# UBX_NORA_B1_SCHEM_0006_Accessories.net
KiCad netlist of a schematic drawn in Altium Designer
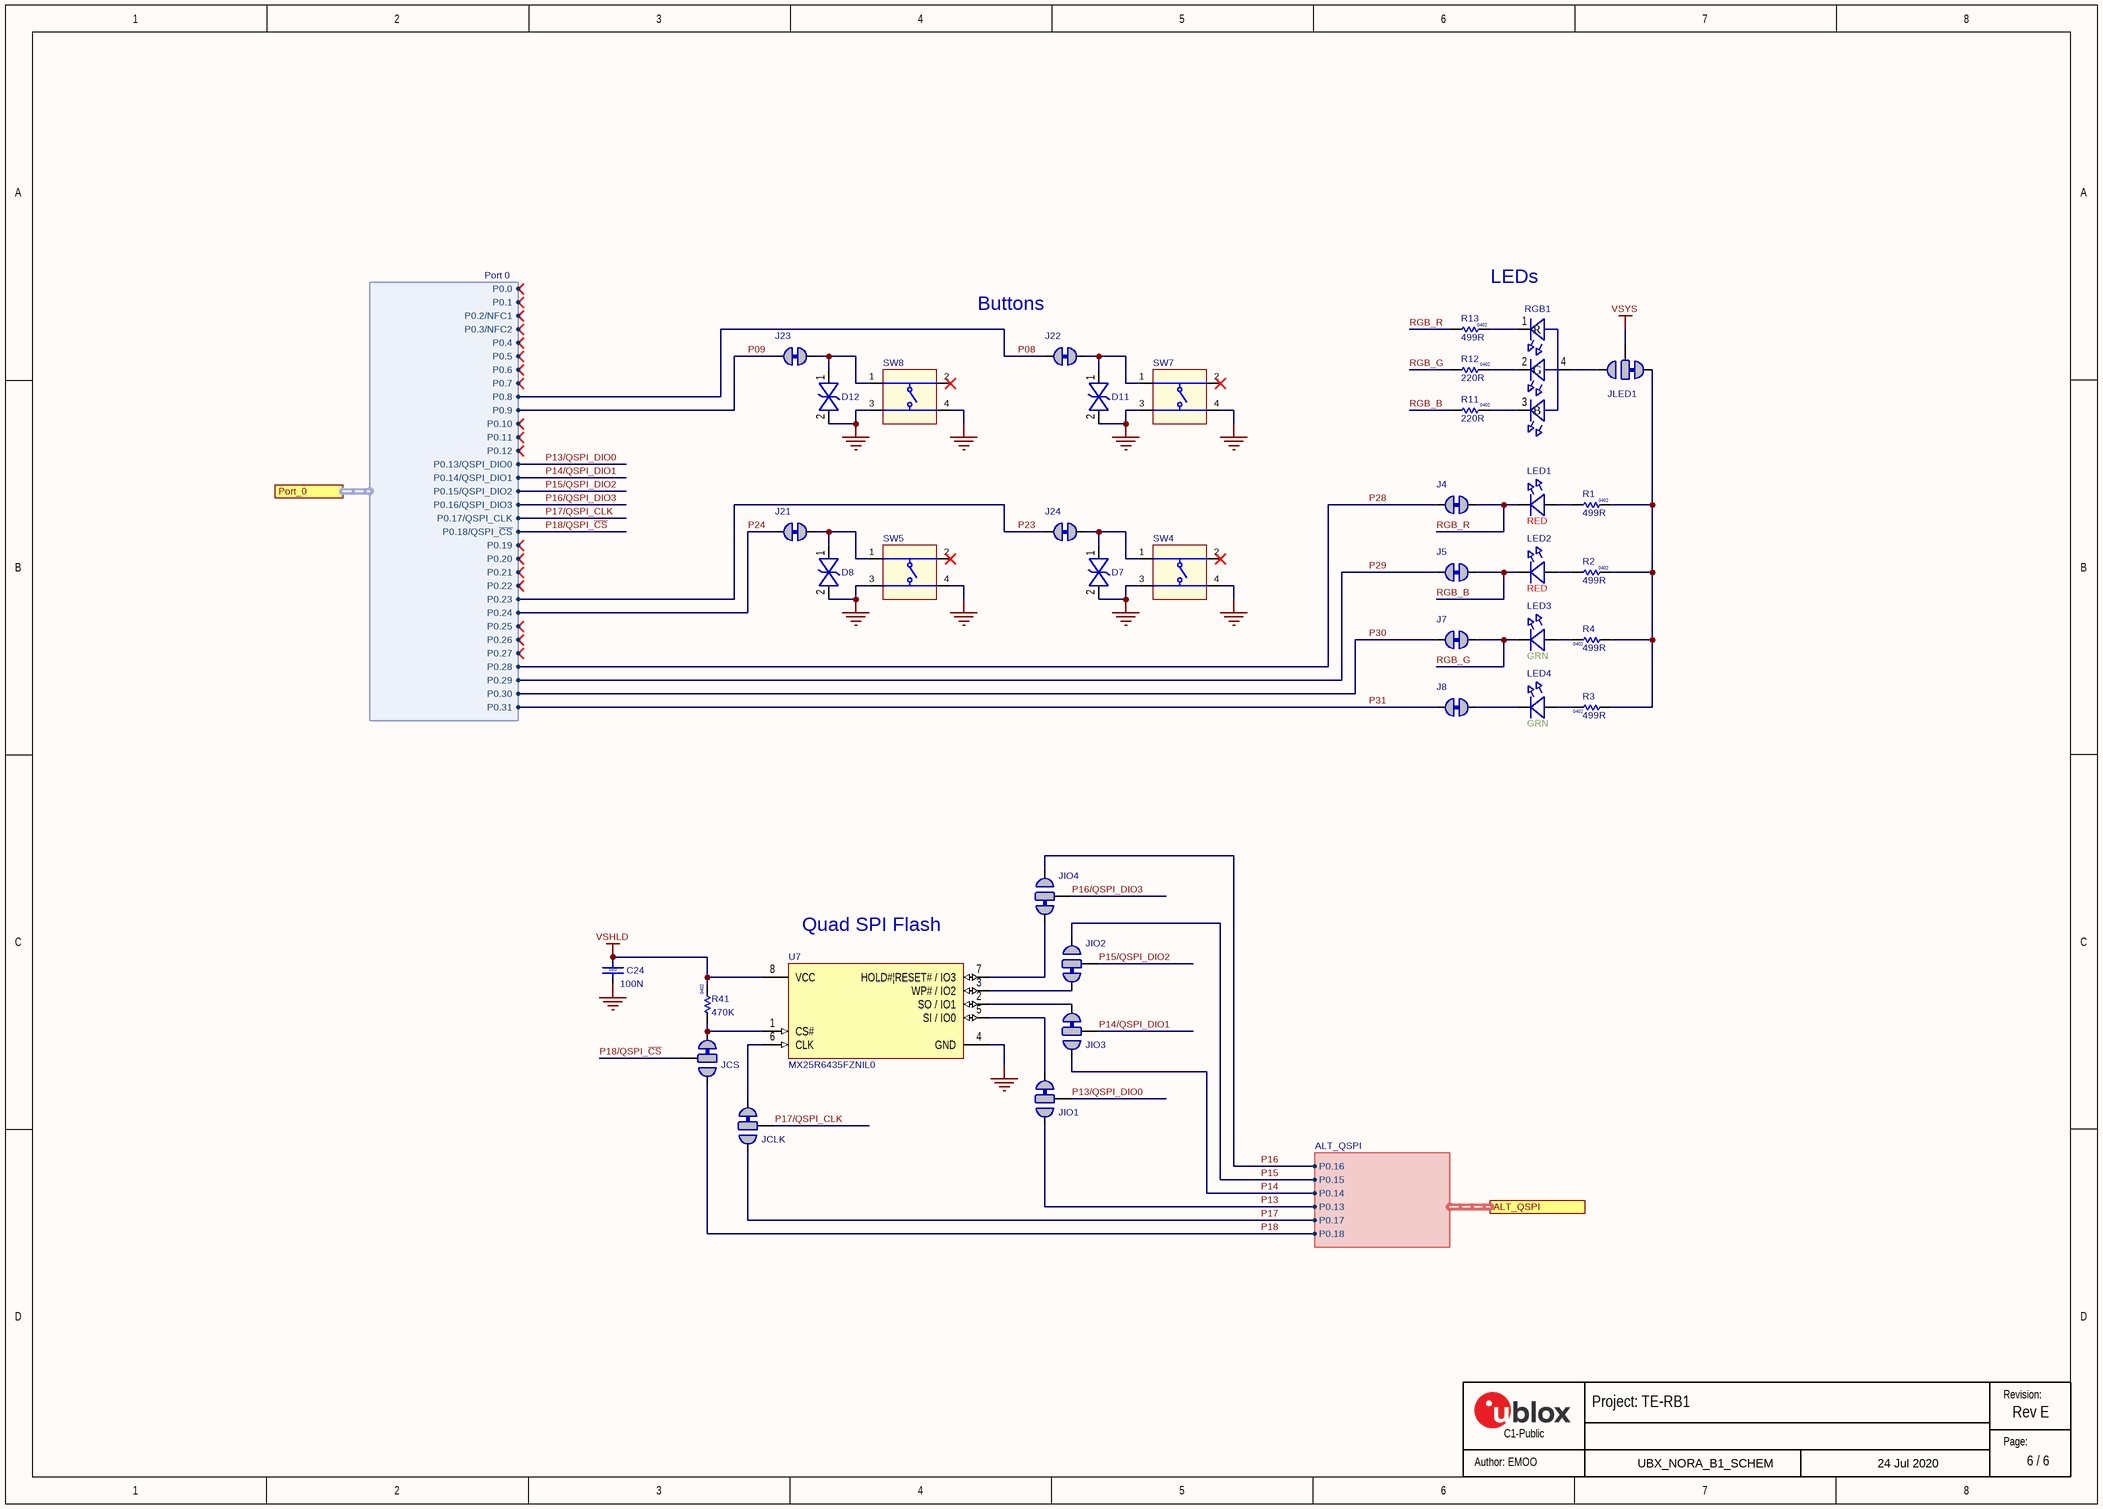
[diagram p0: UBX_NORA_B1_SCHEM_0006_Accessories.SchDoc]

(export (version "E")
  (design (tool "Eeschema 10.0.6"))
  (components
    (comp (ref "C24")
      (value "100N")
      (footprint "Cap 0402 HD")
      (description "CAP CER X5R 0402 100N 10% 10V")
      (fields
        (field (name "SIZE") "0402")
        (field (name "PART NUMBER") "UBXH01-2021002")
        (field (name "TOLERANCE") "10%")
        (field (name "EDITOR") "roland.rust")
        (field (name "RELEASED BY") "roland.rust")
      )
      (libsource (lib "UBX_Parts_DB_Lib") (part "Cap Chip"))
    )
    (comp (ref "D7")
      (value "UBXH07-0000034")
      (footprint "SOD-923")
      (description "ESD PROTECTION DIODE ULTRA LOW LEAKAGE SOD923 ON SEMI 3V3")
      (fields
        (field (name "MANUFACTURER") "ON Semiconductor")
        (field (name "EDITOR") "pierpaolo.arban")
        (field (name "RELEASED BY") "dario.antonaz")
      )
      (libsource (lib "UBX_Parts_DB_Lib") (part "Diode_TVS"))
    )
    (comp (ref "D8")
      (value "UBXH07-0000034")
      (footprint "SOD-923")
      (description "ESD PROTECTION DIODE ULTRA LOW LEAKAGE SOD923 ON SEMI 3V3")
      (fields
        (field (name "MANUFACTURER") "ON Semiconductor")
        (field (name "EDITOR") "pierpaolo.arban")
        (field (name "RELEASED BY") "dario.antonaz")
      )
      (libsource (lib "UBX_Parts_DB_Lib") (part "Diode_TVS"))
    )
    (comp (ref "D11")
      (value "UBXH07-0000034")
      (footprint "SOD-923")
      (description "ESD PROTECTION DIODE ULTRA LOW LEAKAGE SOD923 ON SEMI 3V3")
      (fields
        (field (name "MANUFACTURER") "ON Semiconductor")
        (field (name "EDITOR") "pierpaolo.arban")
        (field (name "RELEASED BY") "dario.antonaz")
      )
      (libsource (lib "UBX_Parts_DB_Lib") (part "Diode_TVS"))
    )
    (comp (ref "D12")
      (value "UBXH07-0000034")
      (footprint "SOD-923")
      (description "ESD PROTECTION DIODE ULTRA LOW LEAKAGE SOD923 ON SEMI 3V3")
      (fields
        (field (name "MANUFACTURER") "ON Semiconductor")
        (field (name "EDITOR") "pierpaolo.arban")
        (field (name "RELEASED BY") "dario.antonaz")
      )
      (libsource (lib "UBX_Parts_DB_Lib") (part "Diode_TVS"))
    )
    (comp (ref "J4")
      (value "UBXH00-0000084")
      (footprint "Solderbridge-Short")
      (description "SOLDERBRIDGE-SHORT")
      (fields (field (name "EDITOR") "aneeb.sohail"))
      (libsource (lib "UBX_Parts_DB_Lib") (part "Solderbridge-Short"))
    )
    (comp (ref "J5")
      (value "UBXH00-0000084")
      (footprint "Solderbridge-Short")
      (description "SOLDERBRIDGE-SHORT")
      (fields (field (name "EDITOR") "aneeb.sohail"))
      (libsource (lib "UBX_Parts_DB_Lib") (part "Solderbridge-Short"))
    )
    (comp (ref "J7")
      (value "UBXH00-0000084")
      (footprint "Solderbridge-Short")
      (description "SOLDERBRIDGE-SHORT")
      (fields (field (name "EDITOR") "aneeb.sohail"))
      (libsource (lib "UBX_Parts_DB_Lib") (part "Solderbridge-Short"))
    )
    (comp (ref "J8")
      (value "UBXH00-0000084")
      (footprint "Solderbridge-Short")
      (description "SOLDERBRIDGE-SHORT")
      (fields (field (name "EDITOR") "aneeb.sohail"))
      (libsource (lib "UBX_Parts_DB_Lib") (part "Solderbridge-Short"))
    )
    (comp (ref "J21")
      (value "UBXH00-0000084")
      (footprint "Solderbridge-Short")
      (description "SOLDERBRIDGE-SHORT")
      (fields (field (name "EDITOR") "aneeb.sohail"))
      (libsource (lib "UBX_Parts_DB_Lib") (part "Solderbridge-Short"))
    )
    (comp (ref "J22")
      (value "UBXH00-0000084")
      (footprint "Solderbridge-Short")
      (description "SOLDERBRIDGE-SHORT")
      (fields (field (name "EDITOR") "aneeb.sohail"))
      (libsource (lib "UBX_Parts_DB_Lib") (part "Solderbridge-Short"))
    )
    (comp (ref "J23")
      (value "UBXH00-0000084")
      (footprint "Solderbridge-Short")
      (description "SOLDERBRIDGE-SHORT")
      (fields (field (name "EDITOR") "aneeb.sohail"))
      (libsource (lib "UBX_Parts_DB_Lib") (part "Solderbridge-Short"))
    )
    (comp (ref "J24")
      (value "UBXH00-0000084")
      (footprint "Solderbridge-Short")
      (description "SOLDERBRIDGE-SHORT")
      (fields (field (name "EDITOR") "aneeb.sohail"))
      (libsource (lib "UBX_Parts_DB_Lib") (part "Solderbridge-Short"))
    )
    (comp (ref "JCLK")
      (value "UBXH00-0000083")
      (footprint "Solderbridge-Option")
      (description "SOLDERBRIDGE-OPTION")
      (fields (field (name "EDITOR") "aneeb.sohail"))
      (libsource (lib "") (part "Solderbridge-Option_2"))
    )
    (comp (ref "JCS")
      (value "UBXH00-0000083")
      (footprint "Solderbridge-Option")
      (description "SOLDERBRIDGE-OPTION")
      (fields (field (name "EDITOR") "aneeb.sohail"))
      (libsource (lib "") (part "Solderbridge-Option_1"))
    )
    (comp (ref "JIO1")
      (value "UBXH00-0000083")
      (footprint "Solderbridge-Option")
      (description "SOLDERBRIDGE-OPTION")
      (fields (field (name "EDITOR") "aneeb.sohail"))
      (libsource (lib "") (part "Solderbridge-Option_2"))
    )
    (comp (ref "JIO2")
      (value "UBXH00-0000083")
      (footprint "Solderbridge-Option")
      (description "SOLDERBRIDGE-OPTION")
      (fields (field (name "EDITOR") "aneeb.sohail"))
      (libsource (lib "UBX_Parts_DB_Lib") (part "Solderbridge-Option"))
    )
    (comp (ref "JIO3")
      (value "UBXH00-0000083")
      (footprint "Solderbridge-Option")
      (description "SOLDERBRIDGE-OPTION")
      (fields (field (name "EDITOR") "aneeb.sohail"))
      (libsource (lib "") (part "Solderbridge-Option_2"))
    )
    (comp (ref "JIO4")
      (value "UBXH00-0000083")
      (footprint "Solderbridge-Option")
      (description "SOLDERBRIDGE-OPTION")
      (fields (field (name "EDITOR") "aneeb.sohail"))
      (libsource (lib "UBX_Parts_DB_Lib") (part "Solderbridge-Option"))
    )
    (comp (ref "JLED1")
      (value "UBXH00-0000083")
      (footprint "Solderbridge-Option")
      (description "SOLDERBRIDGE-OPTION")
      (fields (field (name "EDITOR") "aneeb.sohail"))
      (libsource (lib "") (part "Solderbridge-Option_3"))
    )
    (comp (ref "LED1")
      (value "UBXH11-0000000")
      (footprint "LED_0603_RED")
      (description "LED SMD 0603 ULTRABRIGHT LITE-ON LTST-C190KRKT RED 30mA")
      (fields
        (field (name "COLOR") "RED")
        (field (name "MANUFACTURER") "Lite-on Technology Corporation")
        (field (name "EDITOR") "massimo.vlacci")
        (field (name "RELEASED BY") "sandro.sestan")
      )
      (libsource (lib "UBX_Parts_DB_Lib") (part "LED_BASE"))
    )
    (comp (ref "LED2")
      (value "UBXH11-0000000")
      (footprint "LED_0603_RED")
      (description "LED SMD 0603 ULTRABRIGHT LITE-ON LTST-C190KRKT RED 30mA")
      (fields
        (field (name "COLOR") "RED")
        (field (name "MANUFACTURER") "Lite-on Technology Corporation")
        (field (name "EDITOR") "massimo.vlacci")
        (field (name "RELEASED BY") "sandro.sestan")
      )
      (libsource (lib "UBX_Parts_DB_Lib") (part "LED_BASE"))
    )
    (comp (ref "LED3")
      (value "UBXH11-0000001")
      (footprint "LED_0603_GREEN")
      (description "LED SMD 0603 GREEN 2.5V 20mA")
      (fields
        (field (name "COLOR") "GRN")
        (field (name "MANUFACTURER") "Kingbright")
        (field (name "EDITOR") "gianni.falleroni")
        (field (name "RELEASED BY") "alex.claville")
      )
      (libsource (lib "UBX_Parts_DB_Lib") (part "LED_BASE"))
    )
    (comp (ref "LED4")
      (value "UBXH11-0000001")
      (footprint "LED_0603_GREEN")
      (description "LED SMD 0603 GREEN 2.5V 20mA")
      (fields
        (field (name "COLOR") "GRN")
        (field (name "MANUFACTURER") "Kingbright")
        (field (name "EDITOR") "gianni.falleroni")
        (field (name "RELEASED BY") "alex.claville")
      )
      (libsource (lib "UBX_Parts_DB_Lib") (part "LED_BASE"))
    )
    (comp (ref "R1")
      (value "499R")
      (footprint "RES 0402 HD")
      (description "RES THICK FILM CHIP 0402 499R 1% 100mW")
      (fields
        (field (name "SIZE") "0402")
        (field (name "PART NUMBER") "UBXH18-0000269")
        (field (name "TOLERANCE") "1%")
        (field (name "EDITOR") "pierpaolo.arban")
      )
      (libsource (lib "UBX_Parts_DB_Lib") (part "Res sm"))
    )
    (comp (ref "R2")
      (value "499R")
      (footprint "RES 0402 HD")
      (description "RES THICK FILM CHIP 0402 499R 1% 100mW")
      (fields
        (field (name "SIZE") "0402")
        (field (name "PART NUMBER") "UBXH18-0000269")
        (field (name "TOLERANCE") "1%")
        (field (name "EDITOR") "pierpaolo.arban")
      )
      (libsource (lib "UBX_Parts_DB_Lib") (part "Res sm"))
    )
    (comp (ref "R3")
      (value "499R")
      (footprint "RES 0402 HD")
      (description "RES THICK FILM CHIP 0402 499R 1% 100mW")
      (fields
        (field (name "SIZE") "0402")
        (field (name "PART NUMBER") "UBXH18-0000269")
        (field (name "TOLERANCE") "1%")
        (field (name "EDITOR") "pierpaolo.arban")
      )
      (libsource (lib "UBX_Parts_DB_Lib") (part "Res sm"))
    )
    (comp (ref "R4")
      (value "499R")
      (footprint "RES 0402 HD")
      (description "RES THICK FILM CHIP 0402 499R 1% 100mW")
      (fields
        (field (name "SIZE") "0402")
        (field (name "PART NUMBER") "UBXH18-0000269")
        (field (name "TOLERANCE") "1%")
        (field (name "EDITOR") "pierpaolo.arban")
      )
      (libsource (lib "UBX_Parts_DB_Lib") (part "Res sm"))
    )
    (comp (ref "R11")
      (value "220R")
      (footprint "RES 0402 HD")
      (description "RES THICK FILM CHIP 0402 220R 5% 100mW")
      (fields
        (field (name "SIZE") "0402")
        (field (name "PART NUMBER") "UBXH18-0008033")
        (field (name "TOLERANCE") "5%")
        (field (name "EDITOR") "roland.rust")
        (field (name "RELEASED BY") "roland.rust")
      )
      (libsource (lib "UBX_Parts_DB_Lib") (part "Res sm"))
    )
    (comp (ref "R12")
      (value "220R")
      (footprint "RES 0402 HD")
      (description "RES THICK FILM CHIP 0402 220R 5% 100mW")
      (fields
        (field (name "SIZE") "0402")
        (field (name "PART NUMBER") "UBXH18-0008033")
        (field (name "TOLERANCE") "5%")
        (field (name "EDITOR") "roland.rust")
        (field (name "RELEASED BY") "roland.rust")
      )
      (libsource (lib "UBX_Parts_DB_Lib") (part "Res sm"))
    )
    (comp (ref "R13")
      (value "499R")
      (footprint "RES 0402 HD")
      (description "RES THICK FILM CHIP 0402 499R 1% 100mW")
      (fields
        (field (name "SIZE") "0402")
        (field (name "PART NUMBER") "UBXH18-0000269")
        (field (name "TOLERANCE") "1%")
        (field (name "EDITOR") "pierpaolo.arban")
      )
      (libsource (lib "UBX_Parts_DB_Lib") (part "Res sm"))
    )
    (comp (ref "R41")
      (value "470K")
      (footprint "RES 0402 HD")
      (description "RES THICK FILM CHIP 0402 470K 5% 100mW")
      (fields
        (field (name "SIZE") "0402")
        (field (name "PART NUMBER") "UBXH18-0008113")
        (field (name "TOLERANCE") "5%")
        (field (name "EDITOR") "martin.frauchiger")
        (field (name "RELEASED BY") "martin.frauchiger")
      )
      (libsource (lib "UBX_Parts_DB_Lib") (part "Res sm"))
    )
    (comp (ref "RGB1")
      (value "UBXH11-0000058")
      (footprint "LED_0606_RGB_4PIN")
      (description "LED SMD RGB 0606 COMMON ANODE LITE-ON LTST-C19HE1WT 5V 20mA")
      (fields
        (field (name "MANUFACTURER") "Lite-on Technology Corporation")
        (field (name "EDITOR") "eric.moog")
      )
      (libsource (lib "UBX_Parts_DB_Lib") (part "LED_RGB_CA_4"))
    )
    (comp (ref "SW4")
      (value "UBXH19-0000035")
      (footprint "SW_TACT_SMT_6mm")
      (description "TACTILE SWITCH SPST SINGLE SMD")
      (fields
        (field (name "MANUFACTURER") "C&K")
        (field (name "EDITOR") "enric.suchanek")
        (field (name "RELEASED BY") "charlotte.biber")
      )
      (libsource (lib "UBX_Parts_DB_Lib") (part "SW_TACT_SPST-NO_4Pin"))
    )
    (comp (ref "SW5")
      (value "UBXH19-0000035")
      (footprint "SW_TACT_SMT_6mm")
      (description "TACTILE SWITCH SPST SINGLE SMD")
      (fields
        (field (name "MANUFACTURER") "C&K")
        (field (name "EDITOR") "enric.suchanek")
        (field (name "RELEASED BY") "charlotte.biber")
      )
      (libsource (lib "UBX_Parts_DB_Lib") (part "SW_TACT_SPST-NO_4Pin"))
    )
    (comp (ref "SW7")
      (value "UBXH19-0000035")
      (footprint "SW_TACT_SMT_6mm")
      (description "TACTILE SWITCH SPST SINGLE SMD")
      (fields
        (field (name "MANUFACTURER") "C&K")
        (field (name "EDITOR") "enric.suchanek")
        (field (name "RELEASED BY") "charlotte.biber")
      )
      (libsource (lib "UBX_Parts_DB_Lib") (part "SW_TACT_SPST-NO_4Pin"))
    )
    (comp (ref "SW8")
      (value "UBXH19-0000035")
      (footprint "SW_TACT_SMT_6mm")
      (description "TACTILE SWITCH SPST SINGLE SMD")
      (fields
        (field (name "MANUFACTURER") "C&K")
        (field (name "EDITOR") "enric.suchanek")
        (field (name "RELEASED BY") "charlotte.biber")
      )
      (libsource (lib "UBX_Parts_DB_Lib") (part "SW_TACT_SPST-NO_4Pin"))
    )
    (comp (ref "U7")
      (value "UBXH13-0000138")
      (footprint "WSON1.27P-8Pin_W-Pad")
      (description "MACRONIX MX25R6435FZNIL0 64MBIT SERIAL QUAD I/O SPI FLASH MEMORY 1.65 - 3.6V 8-WDFN 6X5MM")
      (fields
        (field (name "MANUFACTURER P/N") "MX25R6435FZNIL0")
        (field (name "MANUFACTURER") "Macronix International Co.,Ltd.")
        (field (name "EDITOR") "eric.moog")
      )
      (libsource (lib "UBX_Parts_DB_Lib") (part "SPI_Flash_Memory_8Pin"))
    )
  )
  (nets
    (net (code "4") (name "/P08") (class "Default")
      (node (ref "J22") (pin "2") (pinfunction "2_2") (pintype "passive"))
    )
    (net (code "5") (name "/P09") (class "Default")
      (node (ref "J23") (pin "2") (pinfunction "2_2") (pintype "passive"))
    )
    (net (code "6") (name "/P13") (class "Default")
      (node (ref "JIO1") (pin "3") (pinfunction "3_3") (pintype "passive"))
    )
    (net (code "7") (name "/P13{slash}QSPI_DIO0") (class "Default")
      (node (ref "JIO1") (pin "2") (pinfunction "2_2") (pintype "passive"))
    )
    (net (code "8") (name "/P14") (class "Default")
      (node (ref "JIO3") (pin "3") (pinfunction "3_3") (pintype "passive"))
    )
    (net (code "9") (name "/P14{slash}QSPI_DIO1") (class "Default")
      (node (ref "JIO3") (pin "2") (pinfunction "2_2") (pintype "passive"))
    )
    (net (code "10") (name "/P15") (class "Default")
      (node (ref "JIO2") (pin "3") (pinfunction "3_3") (pintype "passive"))
    )
    (net (code "11") (name "/P15{slash}QSPI_DIO2") (class "Default")
      (node (ref "JIO2") (pin "2") (pinfunction "2_2") (pintype "passive"))
    )
    (net (code "12") (name "/P16") (class "Default")
      (node (ref "JIO4") (pin "3") (pinfunction "3_3") (pintype "passive"))
    )
    (net (code "13") (name "/P16{slash}QSPI_DIO3") (class "Default")
      (node (ref "JIO4") (pin "2") (pinfunction "2_2") (pintype "passive"))
    )
    (net (code "14") (name "/P17") (class "Default")
      (node (ref "JCLK") (pin "3") (pinfunction "3_3") (pintype "passive"))
    )
    (net (code "15") (name "/P17{slash}QSPI_CLK") (class "Default")
      (node (ref "JCLK") (pin "2") (pinfunction "2_2") (pintype "passive"))
    )
    (net (code "16") (name "/P18") (class "Default")
      (node (ref "JCS") (pin "3") (pinfunction "3_3") (pintype "passive"))
    )
    (net (code "17") (name "/P18{slash}QSPI_~{CS}") (class "Default")
      (node (ref "JCS") (pin "2") (pinfunction "2_2") (pintype "passive"))
    )
    (net (code "18") (name "/P23") (class "Default")
      (node (ref "J24") (pin "2") (pinfunction "2_2") (pintype "passive"))
    )
    (net (code "19") (name "/P24") (class "Default")
      (node (ref "J21") (pin "2") (pinfunction "2_2") (pintype "passive"))
    )
    (net (code "20") (name "/P28") (class "Default")
      (node (ref "J4") (pin "2") (pinfunction "2_2") (pintype "passive"))
    )
    (net (code "21") (name "/P29") (class "Default")
      (node (ref "J5") (pin "2") (pinfunction "2_2") (pintype "passive"))
    )
    (net (code "22") (name "/P30") (class "Default")
      (node (ref "J7") (pin "2") (pinfunction "2_2") (pintype "passive"))
    )
    (net (code "23") (name "/P31") (class "Default")
      (node (ref "J8") (pin "2") (pinfunction "2_2") (pintype "passive"))
    )
    (net (code "24") (name "/RGB_B") (class "Default")
      (node (ref "J5") (pin "1") (pinfunction "1_1") (pintype "passive"))
      (node (ref "LED2") (pin "1") (pinfunction "C_1") (pintype "passive"))
      (node (ref "R11") (pin "1") (pinfunction "1_1") (pintype "passive"))
    )
    (net (code "25") (name "/RGB_G") (class "Default")
      (node (ref "J7") (pin "1") (pinfunction "1_1") (pintype "passive"))
      (node (ref "LED3") (pin "1") (pinfunction "C_1") (pintype "passive"))
      (node (ref "R12") (pin "1") (pinfunction "1_1") (pintype "passive"))
    )
    (net (code "26") (name "/RGB_R") (class "Default")
      (node (ref "J4") (pin "1") (pinfunction "1_1") (pintype "passive"))
      (node (ref "LED1") (pin "1") (pinfunction "C_1") (pintype "passive"))
      (node (ref "R13") (pin "1") (pinfunction "1_1") (pintype "passive"))
    )
    (net (code "29") (name "GND") (class "Default")
      (node (ref "C24") (pin "2") (pinfunction "2_2") (pintype "passive"))
      (node (ref "D11") (pin "2") (pintype "passive"))
      (node (ref "D12") (pin "2") (pintype "passive"))
      (node (ref "D7") (pin "2") (pintype "passive"))
      (node (ref "D8") (pin "2") (pintype "passive"))
      (node (ref "SW4") (pin "3") (pinfunction "3_3") (pintype "passive"))
      (node (ref "SW4") (pin "4") (pinfunction "4_4") (pintype "passive"))
      (node (ref "SW5") (pin "3") (pinfunction "3_3") (pintype "passive"))
      (node (ref "SW5") (pin "4") (pinfunction "4_4") (pintype "passive"))
      (node (ref "SW7") (pin "3") (pinfunction "3_3") (pintype "passive"))
      (node (ref "SW7") (pin "4") (pinfunction "4_4") (pintype "passive"))
      (node (ref "SW8") (pin "3") (pinfunction "3_3") (pintype "passive"))
      (node (ref "SW8") (pin "4") (pinfunction "4_4") (pintype "passive"))
      (node (ref "U7") (pin "4") (pinfunction "GND_4") (pintype "power_in"))
    )
    (net (code "30") (name "Net-(D7-Pad1)") (class "Default")
      (node (ref "D7") (pin "1") (pintype "passive"))
      (node (ref "J24") (pin "1") (pinfunction "1_1") (pintype "passive"))
      (node (ref "SW4") (pin "1") (pinfunction "1_1") (pintype "passive"))
    )
    (net (code "31") (name "Net-(D8-Pad1)") (class "Default")
      (node (ref "D8") (pin "1") (pintype "passive"))
      (node (ref "J21") (pin "1") (pinfunction "1_1") (pintype "passive"))
      (node (ref "SW5") (pin "1") (pinfunction "1_1") (pintype "passive"))
    )
    (net (code "32") (name "Net-(D11-Pad1)") (class "Default")
      (node (ref "D11") (pin "1") (pintype "passive"))
      (node (ref "J22") (pin "1") (pinfunction "1_1") (pintype "passive"))
      (node (ref "SW7") (pin "1") (pinfunction "1_1") (pintype "passive"))
    )
    (net (code "33") (name "Net-(D12-Pad1)") (class "Default")
      (node (ref "D12") (pin "1") (pintype "passive"))
      (node (ref "J23") (pin "1") (pinfunction "1_1") (pintype "passive"))
      (node (ref "SW8") (pin "1") (pinfunction "1_1") (pintype "passive"))
    )
    (net (code "34") (name "Net-(JLED1-Pad1)") (class "Default")
      (node (ref "JLED1") (pin "1") (pinfunction "1_1") (pintype "passive"))
      (node (ref "R1") (pin "2") (pinfunction "2_2") (pintype "passive"))
      (node (ref "R2") (pin "2") (pinfunction "2_2") (pintype "passive"))
      (node (ref "R3") (pin "1") (pinfunction "1_1") (pintype "passive"))
      (node (ref "R4") (pin "1") (pinfunction "1_1") (pintype "passive"))
    )
    (net (code "35") (name "Net-(LED1-A)") (class "Default")
      (node (ref "LED1") (pin "2") (pinfunction "A_2") (pintype "passive"))
      (node (ref "R1") (pin "1") (pinfunction "1_1") (pintype "passive"))
    )
    (net (code "36") (name "Net-(LED2-A)") (class "Default")
      (node (ref "LED2") (pin "2") (pinfunction "A_2") (pintype "passive"))
      (node (ref "R2") (pin "1") (pinfunction "1_1") (pintype "passive"))
    )
    (net (code "37") (name "Net-(LED3-A)") (class "Default")
      (node (ref "LED3") (pin "2") (pinfunction "A_2") (pintype "passive"))
      (node (ref "R4") (pin "2") (pinfunction "2_2") (pintype "passive"))
    )
    (net (code "38") (name "Net-(LED4-A)") (class "Default")
      (node (ref "LED4") (pin "2") (pinfunction "A_2") (pintype "passive"))
      (node (ref "R3") (pin "2") (pinfunction "2_2") (pintype "passive"))
    )
    (net (code "39") (name "Net-(LED4-C)") (class "Default")
      (node (ref "J8") (pin "1") (pinfunction "1_1") (pintype "passive"))
      (node (ref "LED4") (pin "1") (pinfunction "C_1") (pintype "passive"))
    )
    (net (code "40") (name "Net-(RGB1-A)") (class "Default")
      (node (ref "JLED1") (pin "3") (pinfunction "3_3") (pintype "passive"))
      (node (ref "RGB1") (pin "4") (pinfunction "A_4") (pintype "passive"))
    )
    (net (code "41") (name "Net-(RGB1-B)") (class "Default")
      (node (ref "R11") (pin "2") (pinfunction "2_2") (pintype "passive"))
      (node (ref "RGB1") (pin "3") (pinfunction "B_3") (pintype "passive"))
    )
    (net (code "42") (name "Net-(RGB1-G)") (class "Default")
      (node (ref "R12") (pin "2") (pinfunction "2_2") (pintype "passive"))
      (node (ref "RGB1") (pin "2") (pinfunction "G_2") (pintype "passive"))
    )
    (net (code "43") (name "Net-(RGB1-R)") (class "Default")
      (node (ref "R13") (pin "2") (pinfunction "2_2") (pintype "passive"))
      (node (ref "RGB1") (pin "1") (pinfunction "R_1") (pintype "passive"))
    )
    (net (code "44") (name "Net-(U7-CLK)") (class "Default")
      (node (ref "JCLK") (pin "1") (pinfunction "1_1") (pintype "passive"))
      (node (ref "U7") (pin "6") (pinfunction "CLK_6") (pintype "input"))
    )
    (net (code "45") (name "Net-(U7-CS#)") (class "Default")
      (node (ref "JCS") (pin "1") (pinfunction "1_1") (pintype "passive"))
      (node (ref "R41") (pin "1") (pinfunction "1_1") (pintype "passive"))
      (node (ref "U7") (pin "1") (pinfunction "CS#_1") (pintype "input"))
    )
    (net (code "46") (name "Net-(U7-HOLD#¦RESET#_{slash}_IO3)") (class "Default")
      (node (ref "JIO4") (pin "1") (pinfunction "1_1") (pintype "passive"))
      (node (ref "U7") (pin "7") (pinfunction "HOLD#¦RESET#_/_IO3_7") (pintype "bidirectional"))
    )
    (net (code "47") (name "Net-(U7-SI_{slash}_IO0)") (class "Default")
      (node (ref "JIO1") (pin "1") (pinfunction "1_1") (pintype "passive"))
      (node (ref "U7") (pin "5") (pinfunction "SI_/_IO0_5") (pintype "bidirectional"))
    )
    (net (code "48") (name "Net-(U7-SO_{slash}_IO1)") (class "Default")
      (node (ref "JIO3") (pin "1") (pinfunction "1_1") (pintype "passive"))
      (node (ref "U7") (pin "2") (pinfunction "SO_/_IO1_2") (pintype "bidirectional"))
    )
    (net (code "49") (name "Net-(U7-WP#_{slash}_IO2)") (class "Default")
      (node (ref "JIO2") (pin "1") (pinfunction "1_1") (pintype "passive"))
      (node (ref "U7") (pin "3") (pinfunction "WP#_/_IO2_3") (pintype "bidirectional"))
    )
    (net (code "50") (name "VSHLD") (class "Default")
      (node (ref "C24") (pin "1") (pinfunction "1_1") (pintype "passive"))
      (node (ref "R41") (pin "2") (pinfunction "2_2") (pintype "passive"))
      (node (ref "U7") (pin "8") (pinfunction "VCC_8") (pintype "power_in"))
    )
    (net (code "51") (name "VSYS") (class "Default")
      (node (ref "JLED1") (pin "2") (pinfunction "2_2") (pintype "passive"))
    )
    (net (code "52") (name "unconnected-(SW4-Pad2)") (class "Default")
      (node (ref "SW4") (pin "2") (pinfunction "2_2") (pintype "passive+no_connect"))
    )
    (net (code "53") (name "unconnected-(SW5-Pad2)") (class "Default")
      (node (ref "SW5") (pin "2") (pinfunction "2_2") (pintype "passive+no_connect"))
    )
    (net (code "54") (name "unconnected-(SW7-Pad2)") (class "Default")
      (node (ref "SW7") (pin "2") (pinfunction "2_2") (pintype "passive+no_connect"))
    )
    (net (code "55") (name "unconnected-(SW8-Pad2)") (class "Default")
      (node (ref "SW8") (pin "2") (pinfunction "2_2") (pintype "passive+no_connect"))
    )
  )
)
